# GateDriverandMosfets.net
KiCad netlist of a schematic drawn in Altium Designer
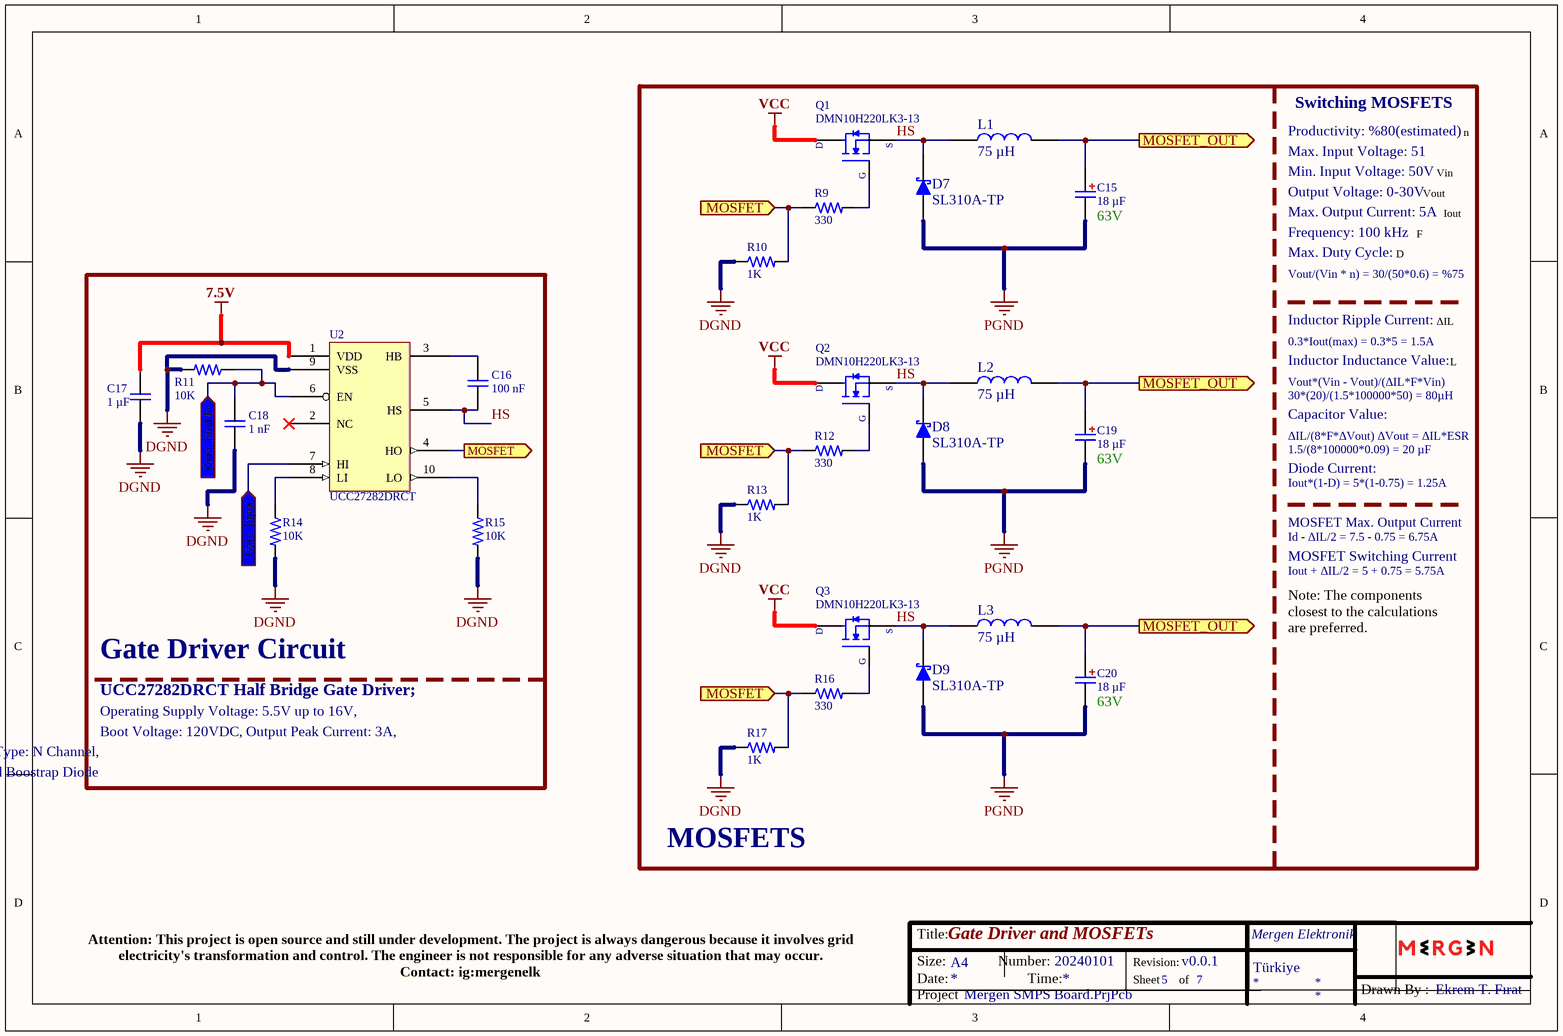
[diagram p0: GateDriverandMosfets.SchDoc]

(export (version "E")
  (design (tool "Eeschema 10.0.6"))
  (components
    (comp (ref "C15")
      (value "18 µF")
      (footprint "MergenElektronik_Capacitors_AluminumElectrolytics_THTs_8x7MM")
      (description "Mergen Elektronik- Capacitors - Aluminum Electrolytics - THTs - 63SXE18M")
      (fields
        (field (name "MANUFACTURER") "Panasonic Electronic Components")
        (field (name "TOLERANCE") "±20%")
        (field (name "VOLTAGE RATED") "63V")
      )
      (libsource (lib "MergenElektronik_Capacitors_AluminumElectrolytics_THTs") (part "MergenElektronik_Capacitors_AluminumElectrolytics_THTs_63SXE18M"))
    )
    (comp (ref "C16")
      (value "100 nF")
      (footprint "MergenElektronik_Capacitors_Ceramics_SMDs_0603_S_NS")
      (description "Mergen Elektronik - Capacitors - Ceramics - SMDs - 0603 - 100 nF - 100V")
      (fields (field (name "MANUFACTURER") "Samsung Electro-Mechanics") (field (name "TOLERANCE") "±10%"))
      (libsource (lib "MergenElektronik_Capacitors_Ceramics_SMDs") (part "MergenElektronik_Capacitors_Ceramic_SMDs_100nF_100V"))
    )
    (comp (ref "C17")
      (value "1 µF")
      (footprint "MergenElektronik_Capacitors_Ceramics_SMDs_1206_S_NS")
      (description "Mergen Elektronik - Capacitors - Ceramics - SMDs - 1206 - 1 µF - 100V")
      (fields (field (name "MANUFACTURER") "Samsung Electro-Mechanics") (field (name "TOLERANCE") "±10%"))
      (libsource (lib "MergenElektronik_Capacitors_Ceramics_SMDs") (part "MergenElektronik_Capacitors_Ceramic_SMDs_1µF_100V"))
    )
    (comp (ref "C18")
      (value "1 nF")
      (footprint "MergenElektronik_Capacitors_Ceramics_SMDs_0402_S_NS")
      (description "Mergen Elektronik - Capacitors - Ceramics - SMDs - 0402 - 1 nF - 50V")
      (fields (field (name "MANUFACTURER") "Murata Electronics") (field (name "TOLERANCE") "±5%"))
      (libsource (lib "MergenElektronik_Capacitors_Ceramics_SMDs") (part "MergenElektronik_Capacitors_Ceramic_SMDs_1nF_50V"))
    )
    (comp (ref "C19")
      (value "18 µF")
      (footprint "MergenElektronik_Capacitors_AluminumElectrolytics_THTs_8x7MM")
      (description "Mergen Elektronik- Capacitors - Aluminum Electrolytics - THTs - 63SXE18M")
      (fields
        (field (name "MANUFACTURER") "Panasonic Electronic Components")
        (field (name "TOLERANCE") "±20%")
        (field (name "VOLTAGE RATED") "63V")
      )
      (libsource (lib "MergenElektronik_Capacitors_AluminumElectrolytics_THTs") (part "MergenElektronik_Capacitors_AluminumElectrolytics_THTs_63SXE18M"))
    )
    (comp (ref "C20")
      (value "18 µF")
      (footprint "MergenElektronik_Capacitors_AluminumElectrolytics_THTs_8x7MM")
      (description "Mergen Elektronik- Capacitors - Aluminum Electrolytics - THTs - 63SXE18M")
      (fields
        (field (name "MANUFACTURER") "Panasonic Electronic Components")
        (field (name "TOLERANCE") "±20%")
        (field (name "VOLTAGE RATED") "63V")
      )
      (libsource (lib "MergenElektronik_Capacitors_AluminumElectrolytics_THTs") (part "MergenElektronik_Capacitors_AluminumElectrolytics_THTs_63SXE18M"))
    )
    (comp (ref "D7")
      (value "SL310A-TP")
      (footprint "MergenElektronik_Diodes_SchottkyDiodes_DO-214AC (SMA)")
      (description "Mergen Elektronik - Diodes - Schottky Diodes - SL310A-TP")
      (fields (field (name "MANUFACTURER") "Micro Commercial Co"))
      (libsource (lib "MergenElektronik_Diodes_SchottkyDiodes") (part "MergenElektronik_Diodes_SchottkyDiodes_SL310A-TP"))
    )
    (comp (ref "D8")
      (value "SL310A-TP")
      (footprint "MergenElektronik_Diodes_SchottkyDiodes_DO-214AC (SMA)")
      (description "Mergen Elektronik - Diodes - Schottky Diodes - SL310A-TP")
      (fields (field (name "MANUFACTURER") "Micro Commercial Co"))
      (libsource (lib "MergenElektronik_Diodes_SchottkyDiodes") (part "MergenElektronik_Diodes_SchottkyDiodes_SL310A-TP"))
    )
    (comp (ref "D9")
      (value "SL310A-TP")
      (footprint "MergenElektronik_Diodes_SchottkyDiodes_DO-214AC (SMA)")
      (description "Mergen Elektronik - Diodes - Schottky Diodes - SL310A-TP")
      (fields (field (name "MANUFACTURER") "Micro Commercial Co"))
      (libsource (lib "MergenElektronik_Diodes_SchottkyDiodes") (part "MergenElektronik_Diodes_SchottkyDiodes_SL310A-TP"))
    )
    (comp (ref "L1")
      (value "75 µH")
      (footprint "MergenElektronik_Inductors_PowerInductors_SMDs_8x8x4mm_Shielded")
      (description "Mergen Elektronik - Inductors - Power Inductors - SMDs - 8x8mm  75-µh - 1.2A")
      (fields (field (name "MANUFACTURER") "Abracon LLC"))
      (libsource (lib "MergenElektronik_Inductors_PowerInductors_SMDs") (part "MergenElektronik_Inductors_PowerInductors_SMDs_ASPI-8040S-750M-T"))
    )
    (comp (ref "L2")
      (value "75 µH")
      (footprint "MergenElektronik_Inductors_PowerInductors_SMDs_8x8x4mm_Shielded")
      (description "Mergen Elektronik - Inductors - Power Inductors - SMDs - 8x8mm  75-µh - 1.2A")
      (fields (field (name "MANUFACTURER") "Abracon LLC"))
      (libsource (lib "MergenElektronik_Inductors_PowerInductors_SMDs") (part "MergenElektronik_Inductors_PowerInductors_SMDs_ASPI-8040S-750M-T"))
    )
    (comp (ref "L3")
      (value "75 µH")
      (footprint "MergenElektronik_Inductors_PowerInductors_SMDs_8x8x4mm_Shielded")
      (description "Mergen Elektronik - Inductors - Power Inductors - SMDs - 8x8mm  75-µh - 1.2A")
      (fields (field (name "MANUFACTURER") "Abracon LLC"))
      (libsource (lib "MergenElektronik_Inductors_PowerInductors_SMDs") (part "MergenElektronik_Inductors_PowerInductors_SMDs_ASPI-8040S-750M-T"))
    )
    (comp (ref "Q1")
      (value "DMN10H220LK3-13")
      (footprint "MergenElektronik_Transistors_Mosfets_TO-252-3(DPAK)")
      (description "Mergen Elektronik - Transistors - Mosfets - DMN10H220LK3-13")
      (fields (field (name "MANUFACTURER") "Diodes Incorporated"))
      (libsource (lib "MergenElektronik_Transistors_Mosfets") (part "MergenElektronik_Transistors_Mosfets_DMN10H220LK3-13"))
    )
    (comp (ref "Q2")
      (value "DMN10H220LK3-13")
      (footprint "MergenElektronik_Transistors_Mosfets_TO-252-3(DPAK)")
      (description "Mergen Elektronik - Transistors - Mosfets - DMN10H220LK3-13")
      (fields (field (name "MANUFACTURER") "Diodes Incorporated"))
      (libsource (lib "MergenElektronik_Transistors_Mosfets") (part "MergenElektronik_Transistors_Mosfets_DMN10H220LK3-13"))
    )
    (comp (ref "Q3")
      (value "DMN10H220LK3-13")
      (footprint "MergenElektronik_Transistors_Mosfets_TO-252-3(DPAK)")
      (description "Mergen Elektronik - Transistors - Mosfets - DMN10H220LK3-13")
      (fields (field (name "MANUFACTURER") "Diodes Incorporated"))
      (libsource (lib "MergenElektronik_Transistors_Mosfets") (part "MergenElektronik_Transistors_Mosfets_DMN10H220LK3-13"))
    )
    (comp (ref "R9")
      (value "330")
      (footprint "MergenElektronik_Resistors_ChipResistors_0603_S_NS")
      (description "Mergen Elektronik - Resistors - Chip Resistors - 0603 - 330R")
      (fields (field (name "MANUFACTURER") "Stackpole Electronics Inc") (field (name "POWER") "1/10W"))
      (libsource (lib "MergenElektronik_Resistors_ChipResistors") (part "MergenElektronik_Resistors_ChipResistors_0603_330R"))
    )
    (comp (ref "R10")
      (value "1K")
      (footprint "MergenElektronik_Resistors_ChipResistors_0603_S_NS")
      (description "Mergen Elektronik - Resistors - Chip Resistors - 0603 - 1K")
      (fields (field (name "MANUFACTURER") "Stackpole Electronics Inc") (field (name "POWER") "1/10W"))
      (libsource (lib "MergenElektronik_Resistors_ChipResistors") (part "MergenElektronik_Resistors_ChipResistors_0603_1K"))
    )
    (comp (ref "R11")
      (value "10K")
      (footprint "MergenElektronik_Resistors_ChipResistors_0603_S_NS")
      (description "Mergen Elektronik - Resistors - Chip Resistors - 0603 - 10K")
      (fields (field (name "MANUFACTURER") "Stackpole Electronics Inc") (field (name "POWER") "1/10W"))
      (libsource (lib "MergenElektronik_Resistors_ChipResistors") (part "MergenElektronik_Resistors_ChipResistors_0603_10K"))
    )
    (comp (ref "R12")
      (value "330")
      (footprint "MergenElektronik_Resistors_ChipResistors_0603_S_NS")
      (description "Mergen Elektronik - Resistors - Chip Resistors - 0603 - 330R")
      (fields (field (name "MANUFACTURER") "Stackpole Electronics Inc") (field (name "POWER") "1/10W"))
      (libsource (lib "MergenElektronik_Resistors_ChipResistors") (part "MergenElektronik_Resistors_ChipResistors_0603_330R"))
    )
    (comp (ref "R13")
      (value "1K")
      (footprint "MergenElektronik_Resistors_ChipResistors_0603_S_NS")
      (description "Mergen Elektronik - Resistors - Chip Resistors - 0603 - 1K")
      (fields (field (name "MANUFACTURER") "Stackpole Electronics Inc") (field (name "POWER") "1/10W"))
      (libsource (lib "MergenElektronik_Resistors_ChipResistors") (part "MergenElektronik_Resistors_ChipResistors_0603_1K"))
    )
    (comp (ref "R14")
      (value "10K")
      (footprint "MergenElektronik_Resistors_ChipResistors_0603_S_NS")
      (description "Mergen Elektronik - Resistors - Chip Resistors - 0603 - 10K")
      (fields (field (name "MANUFACTURER") "Stackpole Electronics Inc") (field (name "POWER") "1/10W"))
      (libsource (lib "MergenElektronik_Resistors_ChipResistors") (part "MergenElektronik_Resistors_ChipResistors_0603_10K"))
    )
    (comp (ref "R15")
      (value "10K")
      (footprint "MergenElektronik_Resistors_ChipResistors_0603_S_NS")
      (description "Mergen Elektronik - Resistors - Chip Resistors - 0603 - 10K")
      (fields (field (name "MANUFACTURER") "Stackpole Electronics Inc") (field (name "POWER") "1/10W"))
      (libsource (lib "MergenElektronik_Resistors_ChipResistors") (part "MergenElektronik_Resistors_ChipResistors_0603_10K"))
    )
    (comp (ref "R16")
      (value "330")
      (footprint "MergenElektronik_Resistors_ChipResistors_0603_S_NS")
      (description "Mergen Elektronik - Resistors - Chip Resistors - 0603 - 330R")
      (fields (field (name "MANUFACTURER") "Stackpole Electronics Inc") (field (name "POWER") "1/10W"))
      (libsource (lib "MergenElektronik_Resistors_ChipResistors") (part "MergenElektronik_Resistors_ChipResistors_0603_330R"))
    )
    (comp (ref "R17")
      (value "1K")
      (footprint "MergenElektronik_Resistors_ChipResistors_0603_S_NS")
      (description "Mergen Elektronik - Resistors - Chip Resistors - 0603 - 1K")
      (fields (field (name "MANUFACTURER") "Stackpole Electronics Inc") (field (name "POWER") "1/10W"))
      (libsource (lib "MergenElektronik_Resistors_ChipResistors") (part "MergenElektronik_Resistors_ChipResistors_0603_1K"))
    )
    (comp (ref "U2")
      (value "UCC27282DRCT")
      (footprint "MergenElektronik_Logics_GateDrivers_10VSON")
      (description "Mergen Elektronik - Logics - Gate Drivers - UCC27282DRCT")
      (fields (field (name "MANUFACTURER") "Texas Instruments"))
      (libsource (lib "MergenElektronik_Logics_GateDrivers") (part "MergenElektronik_Logics_GateDrivers_UCC27282DRCT"))
    )
  )
  (nets
    (net (code "1") (name "/Gate_Enable") (class "Default")
      (node (ref "C18") (pin "1") (pinfunction "1_1") (pintype "passive"))
      (node (ref "R11") (pin "1") (pinfunction "1_1") (pintype "passive"))
      (node (ref "U2") (pin "6") (pinfunction "EN_6") (pintype "passive"))
    )
    (net (code "2") (name "/Gate_Input") (class "Default")
      (node (ref "U2") (pin "7") (pinfunction "HI_7") (pintype "input"))
    )
    (net (code "3") (name "/HS") (class "Default")
      (node (ref "C16") (pin "2") (pinfunction "2_2") (pintype "passive"))
      (node (ref "D7") (pin "2") (pinfunction "KATOT_2") (pintype "passive"))
      (node (ref "D8") (pin "2") (pinfunction "KATOT_2") (pintype "passive"))
      (node (ref "D9") (pin "2") (pinfunction "KATOT_2") (pintype "passive"))
      (node (ref "L1") (pin "1") (pinfunction "1_1") (pintype "passive"))
      (node (ref "L2") (pin "1") (pinfunction "1_1") (pintype "passive"))
      (node (ref "L3") (pin "1") (pinfunction "1_1") (pintype "passive"))
      (node (ref "Q1") (pin "2") (pinfunction "Source_2") (pintype "passive"))
      (node (ref "Q2") (pin "2") (pinfunction "Source_2") (pintype "passive"))
      (node (ref "Q3") (pin "2") (pinfunction "Source_2") (pintype "passive"))
      (node (ref "U2") (pin "5") (pinfunction "HS_5") (pintype "power_in"))
    )
    (net (code "4") (name "/MOSFET") (class "Default")
      (node (ref "R10") (pin "2") (pinfunction "2_2") (pintype "passive"))
      (node (ref "R12") (pin "1") (pinfunction "1_1") (pintype "passive"))
      (node (ref "R13") (pin "2") (pinfunction "2_2") (pintype "passive"))
      (node (ref "R16") (pin "1") (pinfunction "1_1") (pintype "passive"))
      (node (ref "R17") (pin "2") (pinfunction "2_2") (pintype "passive"))
      (node (ref "R9") (pin "1") (pinfunction "1_1") (pintype "passive"))
      (node (ref "U2") (pin "4") (pinfunction "HO_4") (pintype "output"))
    )
    (net (code "5") (name "/MOSFET_OUT") (class "Default")
      (node (ref "C15") (pin "ANOT") (pinfunction "2_ANOT") (pintype "passive"))
      (node (ref "C19") (pin "ANOT") (pinfunction "2_ANOT") (pintype "passive"))
      (node (ref "C20") (pin "ANOT") (pinfunction "2_ANOT") (pintype "passive"))
      (node (ref "L1") (pin "2") (pinfunction "2_2") (pintype "passive"))
      (node (ref "L2") (pin "2") (pinfunction "2_2") (pintype "passive"))
      (node (ref "L3") (pin "2") (pinfunction "2_2") (pintype "passive"))
    )
    (net (code "6") (name "7.5V") (class "Default")
      (node (ref "C17") (pin "1") (pinfunction "1_1") (pintype "passive"))
      (node (ref "U2") (pin "1") (pinfunction "VDD_1") (pintype "power_in"))
    )
    (net (code "7") (name "DGND") (class "Default")
      (node (ref "C17") (pin "2") (pinfunction "2_2") (pintype "passive"))
      (node (ref "C18") (pin "2") (pinfunction "2_2") (pintype "passive"))
      (node (ref "R10") (pin "1") (pinfunction "1_1") (pintype "passive"))
      (node (ref "R11") (pin "2") (pinfunction "2_2") (pintype "passive"))
      (node (ref "R13") (pin "1") (pinfunction "1_1") (pintype "passive"))
      (node (ref "R14") (pin "2") (pinfunction "2_2") (pintype "passive"))
      (node (ref "R15") (pin "2") (pinfunction "2_2") (pintype "passive"))
      (node (ref "R17") (pin "1") (pinfunction "1_1") (pintype "passive"))
      (node (ref "U2") (pin "9") (pinfunction "VSS_9") (pintype "power_in"))
    )
    (net (code "8") (name "Net-(Q1-Gate)") (class "Default")
      (node (ref "Q1") (pin "1") (pinfunction "Gate_1") (pintype "passive"))
      (node (ref "R9") (pin "2") (pinfunction "2_2") (pintype "passive"))
    )
    (net (code "9") (name "Net-(Q2-Gate)") (class "Default")
      (node (ref "Q2") (pin "1") (pinfunction "Gate_1") (pintype "passive"))
      (node (ref "R12") (pin "2") (pinfunction "2_2") (pintype "passive"))
    )
    (net (code "10") (name "Net-(Q3-Gate)") (class "Default")
      (node (ref "Q3") (pin "1") (pinfunction "Gate_1") (pintype "passive"))
      (node (ref "R16") (pin "2") (pinfunction "2_2") (pintype "passive"))
    )
    (net (code "11") (name "Net-(U2-HB)") (class "Default")
      (node (ref "C16") (pin "1") (pinfunction "1_1") (pintype "passive"))
      (node (ref "U2") (pin "3") (pinfunction "HB_3") (pintype "power_in"))
    )
    (net (code "12") (name "Net-(U2-LI)") (class "Default")
      (node (ref "R14") (pin "1") (pinfunction "1_1") (pintype "passive"))
      (node (ref "U2") (pin "8") (pinfunction "LI_8") (pintype "input"))
    )
    (net (code "13") (name "Net-(U2-LO)") (class "Default")
      (node (ref "R15") (pin "1") (pinfunction "1_1") (pintype "passive"))
      (node (ref "U2") (pin "10") (pinfunction "LO_10") (pintype "output"))
    )
    (net (code "14") (name "PGND") (class "Default")
      (node (ref "C15") (pin "KATOT") (pinfunction "1_KATOT") (pintype "passive"))
      (node (ref "C19") (pin "KATOT") (pinfunction "1_KATOT") (pintype "passive"))
      (node (ref "C20") (pin "KATOT") (pinfunction "1_KATOT") (pintype "passive"))
      (node (ref "D7") (pin "1") (pinfunction "ANOT_1") (pintype "passive"))
      (node (ref "D8") (pin "1") (pinfunction "ANOT_1") (pintype "passive"))
      (node (ref "D9") (pin "1") (pinfunction "ANOT_1") (pintype "passive"))
    )
    (net (code "15") (name "VCC") (class "Default")
      (node (ref "Q1") (pin "3") (pinfunction "Drain_3") (pintype "passive"))
      (node (ref "Q2") (pin "3") (pinfunction "Drain_3") (pintype "passive"))
      (node (ref "Q3") (pin "3") (pinfunction "Drain_3") (pintype "passive"))
    )
    (net (code "16") (name "unconnected-(U2-NC-Pad2)") (class "Default")
      (node (ref "U2") (pin "2") (pinfunction "NC_2") (pintype "passive+no_connect"))
    )
  )
)
